# 12V_Buck_Motor.net
KiCad netlist of a schematic drawn in Altium Designer
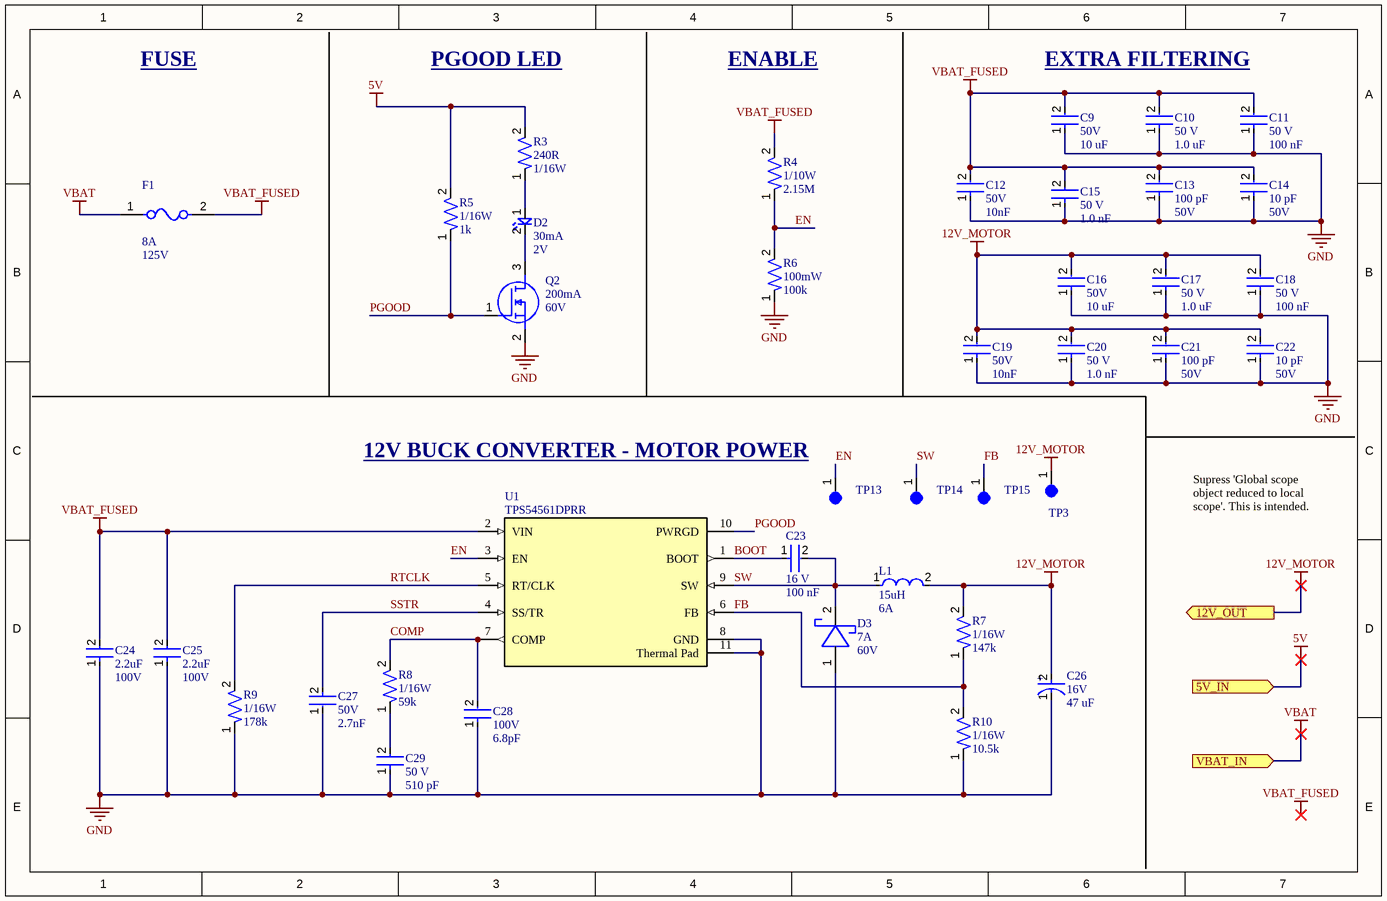
[diagram p0: 12V_Buck_Motor.SchDoc]

(export (version "E")
  (design (tool "Eeschema 10.0.6"))
  (components
    (comp (ref "C9")
      (value "CL32B106KBJNNNE")
      (footprint "CAP-1210")
      (description "CAP CER 10UF 50V X7R 1210")
      (fields (field (name "VOLTAGE") "50V") (field (name "CAPACITANCE") "10 uF"))
      (libsource (lib "JLC_25") (part "CAP-10U-0002"))
    )
    (comp (ref "C10")
      (value "CC0805KKX7R9BB105")
      (footprint "CAP-0805")
      (description "CAP CER 1UF 50V X7R 0805")
      (fields (field (name "VOLTAGE") "50 V") (field (name "CAPACITANCE") "1.0 uF"))
      (libsource (lib "JLC_25") (part "CAP-1U-0001"))
    )
    (comp (ref "C11")
      (value "CC0805KRX7R9BB104")
      (footprint "CAP-0805")
      (description "CAP CER 0.1UF 50V X7R 0805")
      (fields (field (name "VOLTAGE RATING") "50 V") (field (name "CAPACITANCE") "100 nF"))
      (libsource (lib "JLC_25") (part "CAP-0.1U-0002"))
    )
    (comp (ref "C12")
      (value "GRM2195C1H103JA01D")
      (footprint "CAP-0805")
      (description "CAP CER 10000PF 50V C0G/NP0 0805")
      (fields (field (name "VOLTAGE") "50V") (field (name "CAPACITANCE") "10nF"))
      (libsource (lib "JLC_25") (part "CAP-10N-0001"))
    )
    (comp (ref "C13")
      (value "CC0402JRNPO9BN101")
      (footprint "CAP-0402")
      (description "CAP CER 100PF 50V C0G/NPO 0402")
      (fields (field (name "CAPACITANCE") "100 pF") (field (name "VOLTAGE") "50V"))
      (libsource (lib "JLC_25") (part "CAP-100P-0001"))
    )
    (comp (ref "C14")
      (value "CC0402JRNPO9BN100")
      (footprint "CAP-0402")
      (description "CAP CER 10PF 50V C0G/NPO 0402")
      (fields (field (name "CAPACITANCE") "10 pF") (field (name "VOLTAGE") "50V"))
      (libsource (lib "JLC_25") (part "CAP-10P-0001"))
    )
    (comp (ref "C15")
      (value "CC0402KRX7R9BB102")
      (footprint "CAP-0402")
      (description "CAP CER 1000PF 50V X7R 0402")
      (fields (field (name "VOLTAGE") "50 V") (field (name "CAPACITANCE") "1.0 nF"))
      (libsource (lib "JLC_25") (part "CAP-1N-0001"))
    )
    (comp (ref "C16")
      (value "CL32B106KBJNNNE")
      (footprint "CAP-1210")
      (description "CAP CER 10UF 50V X7R 1210")
      (fields (field (name "VOLTAGE") "50V") (field (name "CAPACITANCE") "10 uF"))
      (libsource (lib "JLC_25") (part "CAP-10U-0002"))
    )
    (comp (ref "C17")
      (value "CC0805KKX7R9BB105")
      (footprint "CAP-0805")
      (description "CAP CER 1UF 50V X7R 0805")
      (fields (field (name "VOLTAGE") "50 V") (field (name "CAPACITANCE") "1.0 uF"))
      (libsource (lib "JLC_25") (part "CAP-1U-0001"))
    )
    (comp (ref "C18")
      (value "CC0805KRX7R9BB104")
      (footprint "CAP-0805")
      (description "CAP CER 0.1UF 50V X7R 0805")
      (fields (field (name "VOLTAGE RATING") "50 V") (field (name "CAPACITANCE") "100 nF"))
      (libsource (lib "JLC_25") (part "CAP-0.1U-0002"))
    )
    (comp (ref "C19")
      (value "GRM2195C1H103JA01D")
      (footprint "CAP-0805")
      (description "CAP CER 10000PF 50V C0G/NP0 0805")
      (fields (field (name "VOLTAGE") "50V") (field (name "CAPACITANCE") "10nF"))
      (libsource (lib "JLC_25") (part "CAP-10N-0001"))
    )
    (comp (ref "C20")
      (value "CC0402KRX7R9BB102")
      (footprint "CAP-0402")
      (description "CAP CER 1000PF 50V X7R 0402")
      (fields (field (name "VOLTAGE") "50 V") (field (name "CAPACITANCE") "1.0 nF"))
      (libsource (lib "JLC_25") (part "CAP-1N-0001"))
    )
    (comp (ref "C21")
      (value "CC0402JRNPO9BN101")
      (footprint "CAP-0402")
      (description "CAP CER 100PF 50V C0G/NPO 0402")
      (fields (field (name "CAPACITANCE") "100 pF") (field (name "VOLTAGE") "50V"))
      (libsource (lib "JLC_25") (part "CAP-100P-0001"))
    )
    (comp (ref "C22")
      (value "CC0402JRNPO9BN100")
      (footprint "CAP-0402")
      (description "CAP CER 10PF 50V C0G/NPO 0402")
      (fields (field (name "CAPACITANCE") "10 pF") (field (name "VOLTAGE") "50V"))
      (libsource (lib "JLC_25") (part "CAP-10P-0001"))
    )
    (comp (ref "C23")
      (value "CC0402KRX7R7BB104")
      (footprint "CAP-0402")
      (description "CAP CER 0.1UF 16V X7R 0402")
      (fields (field (name "VOLTAGE RATING") "16 V") (field (name "CAPACITANCE") "100 nF"))
      (libsource (lib "JLC_25") (part "CAP-0.1U-0001"))
    )
    (comp (ref "C24")
      (value "CC1206KKX7R0BB225")
      (footprint "CAP-1206")
      (description "CAP CER 2.2UF 100V X7R 1206")
      (fields (field (name "CAPACITANCE") "2.2uF") (field (name "VOLTAGE") "100V"))
      (libsource (lib "JLC_25") (part "CAP-2.2U-0001"))
    )
    (comp (ref "C25")
      (value "CC1206KKX7R0BB225")
      (footprint "CAP-1206")
      (description "CAP CER 2.2UF 100V X7R 1206")
      (fields (field (name "CAPACITANCE") "2.2uF") (field (name "VOLTAGE") "100V"))
      (libsource (lib "JLC_25") (part "CAP-2.2U-0001"))
    )
    (comp (ref "C26")
      (value "16SVPG47M")
      (footprint "CAP-47U-0001")
      (description "CAP ALUM POLY 47UF 20% 16V SMD")
      (fields (field (name "VOLTAGE") "16V") (field (name "CAPACITANCE") "47 uF"))
      (libsource (lib "JLC_25") (part "CAP-47U-0001"))
    )
    (comp (ref "C27")
      (value "GRM2165C1H272JA01D")
      (footprint "CAP-0805")
      (description "CAP CER 2700PF 50V C0G/NP0 0805")
      (fields (field (name "VOLTAGE") "50V") (field (name "CAPACITANCE") "2.7nF"))
      (libsource (lib "JLC_25") (part "CAP-2.7N-0001"))
    )
    (comp (ref "C28")
      (value "CC0603CRNPO0BN6R8")
      (footprint "CAP-0603")
      (description "CAP CER 6.8PF 100V C0G/NPO 0603")
      (fields (field (name "VOLTAGE") "100V") (field (name "CAPACITANCE") "6.8pF"))
      (libsource (lib "JLC_25") (part "CAP-6.8P-0001"))
    )
    (comp (ref "C29")
      (value "0402N511J500CT")
      (footprint "CAP-0402")
      (description "CAP CER 510PF 50V C0G/NP0 0402")
      (fields (field (name "VOLTAGE") "50 V") (field (name "CAPACITANCE") "510 pF"))
      (libsource (lib "JLC_25") (part "CAP-510P-0001"))
    )
    (comp (ref "D2")
      (value "BL-HKC36G-AV-TRB")
      (footprint "LED-0603")
      (description "LED YELLOW CLEAR 0603 SMD")
      (fields (field (name "FORWARD CURRENT") "30mA") (field (name "FORWARD VOLTAGE") "2V"))
      (libsource (lib "JLC_25") (part "LED-0001"))
    )
    (comp (ref "D3")
      (value "PDS760-13")
      (footprint "DO-POWERDI5")
      (description "DIODE SCHOTTKY 60V 7A POWERDI5")
      (fields (field (name "FORWARD CURRENT") "7A") (field (name "REVERSE VOLTAGE (DC)") "60V"))
      (libsource (lib "JLC_25") (part "DIO-SCHOTTKY-0001"))
    )
    (comp (ref "F1")
      (value "01550900M")
      (footprint "FUSE-0001")
      (description "FUSE BLOK CARTRIDGE 125V 10A SMD")
      (fields (field (name "FUSE CURRENT") "8A") (field (name "VOLTAGE RATING") "125V"))
      (libsource (lib "JLC_25") (part "FUSE-0001"))
    )
    (comp (ref "L1")
      (value "CSAD1010-150M")
      (footprint "IND-15U-0002")
      (description "SMD MOLDING POWER CHOKE")
      (fields (field (name "INDUCTANCE") "15uH") (field (name "CURRENT RATING") "6A"))
      (libsource (lib "JLC_25") (part "IND-15U-0002-NoJLC"))
    )
    (comp (ref "Q2")
      (value "T2N7002AK,LM")
      (footprint "IC-SOT23-3")
      (description "MOSFET N-CH 60V 200MA SOT23")
      (fields (field (name "CONTINUOUS CURRENT") "200mA") (field (name "VOLTAGE") "60V"))
      (libsource (lib "JLC_25") (part "NMOS-200MA-0001"))
    )
    (comp (ref "R3")
      (value "RC0402FR-07240RL")
      (footprint "RES-0402")
      (description "240R 0.063W 1% 0402 (1005 Metric)  SMD")
      (fields
        (field (name "TOLERANCE") "1%")
        (field (name "RESISTANCE") "240R")
        (field (name "POWER") "1/16W")
      )
      (libsource (lib "JLC_25") (part "RES-240-0001"))
    )
    (comp (ref "R4")
      (value "RC0603FR-072M15L")
      (footprint "RES-0603")
      (description "RES SMD 2.15M OHM 1% 1/10W 0603")
      (fields
        (field (name "TOLERANCE") "1%")
        (field (name "POWER") "1/10W")
        (field (name "RESISTANCE") "2.15M")
      )
      (libsource (lib "JLC_25") (part "RES-2.15M-0001"))
    )
    (comp (ref "R5")
      (value "RC0402FR-071KL")
      (footprint "RES-0402")
      (description "RES 1K OHM 1% 1/16W 0402")
      (fields (field (name "TOLERANCE") "1%") (field (name "POWER") "1/16W") (field (name "RESISTANCE") "1k"))
      (libsource (lib "JLC_25") (part "RES-1k-0001"))
    )
    (comp (ref "R6")
      (value "RC0603FR-07100KL")
      (footprint "RES-0603")
      (description "RES SMD 100K OHM 1% 1/10W 0603")
      (fields
        (field (name "TOLERANCE") "1%")
        (field (name "POWER") "100mW")
        (field (name "RESISTANCE") "100k")
      )
      (libsource (lib "JLC_25") (part "RES-100k-0001"))
    )
    (comp (ref "R7")
      (value "RC0402FR-07147KL")
      (footprint "RES-0402")
      (description "RES 147K OHM 1% 1/16W 0402")
      (fields
        (field (name "TOLERANCE") "1%")
        (field (name "POWER") "1/16W")
        (field (name "RESISTANCE") "147k")
      )
      (libsource (lib "JLC_25") (part "RES-147k-0001"))
    )
    (comp (ref "R8")
      (value "RC0402FR-0759KL")
      (footprint "RES-0402")
      (description "RES 59K OHM 1% 1/16W 0402")
      (fields
        (field (name "TOLERANCE") "1%")
        (field (name "POWER") "1/16W")
        (field (name "RESISTANCE") "59k")
      )
      (libsource (lib "JLC_25") (part "RES-59k-0001"))
    )
    (comp (ref "R9")
      (value "RTT021783FTH")
      (footprint "RES-0402")
      (description "62.5mW Thick Film Resistors 50V ±100ppm/℃ ±1% 178kΩ 0402 Chip Resistor - Surface Mount ROHS")
      (fields
        (field (name "TOLERANCE") "1%")
        (field (name "POWER") "1/16W")
        (field (name "RESISTANCE") "178k")
      )
      (libsource (lib "JLC_25") (part "RES-178k-0001"))
    )
    (comp (ref "R10")
      (value "RC0402FR-0710K5L")
      (footprint "RES-0402")
      (description "RES 10.5K OHM 1% 1/16W 0402")
      (fields
        (field (name "TOLERANCE") "1%")
        (field (name "POWER") "1/16W")
        (field (name "RESISTANCE") "10.5k")
      )
      (libsource (lib "JLC_25") (part "RES-10.5k-0001"))
    )
    (comp (ref "TP3")
      (value "5003")
      (footprint "TEST-POINT-0001")
      (description "Oranange PC Test Point, Miniature Phoisphor Bronze Silver Plating Through Hole Mounting Type")
      (libsource (lib "*") (part "TEST-POINT-0001"))
    )
    (comp (ref "TP13")
      (value "5003")
      (footprint "TEST-POINT-0001")
      (description "Oranange PC Test Point, Miniature Phoisphor Bronze Silver Plating Through Hole Mounting Type")
      (libsource (lib "*") (part "TEST-POINT-0001"))
    )
    (comp (ref "TP14")
      (value "5003")
      (footprint "TEST-POINT-0001")
      (description "Oranange PC Test Point, Miniature Phoisphor Bronze Silver Plating Through Hole Mounting Type")
      (libsource (lib "*") (part "TEST-POINT-0001"))
    )
    (comp (ref "TP15")
      (value "5003")
      (footprint "TEST-POINT-0001")
      (description "Oranange PC Test Point, Miniature Phoisphor Bronze Silver Plating Through Hole Mounting Type")
      (libsource (lib "*") (part "TEST-POINT-0001"))
    )
    (comp (ref "U1")
      (value "TPS54561DPRR")
      (footprint "IC-10WSON")
      (description "IC REG BUCK ADJ 5A 10WSON")
      (libsource (lib "JLC_25") (part "IC-BUCK-0001"))
    )
  )
  (nets
    (net (code "1") (name "/BOOT") (class "Default")
      (node (ref "C23") (pin "1") (pinfunction "1_1") (pintype "passive"))
      (node (ref "U1") (pin "1") (pinfunction "BOOT_1") (pintype "output"))
    )
    (net (code "2") (name "/COMP") (class "Default")
      (node (ref "C28") (pin "2") (pinfunction "2_2") (pintype "passive"))
      (node (ref "R8") (pin "2") (pinfunction "2_2") (pintype "passive"))
      (node (ref "U1") (pin "7") (pinfunction "COMP_7") (pintype "output"))
    )
    (net (code "3") (name "/EN") (class "Default")
      (node (ref "R4") (pin "1") (pinfunction "1_1") (pintype "passive"))
      (node (ref "R6") (pin "2") (pinfunction "2_2") (pintype "passive"))
      (node (ref "TP13") (pin "1") (pinfunction "0_1") (pintype "passive"))
      (node (ref "U1") (pin "3") (pinfunction "EN_3") (pintype "input"))
    )
    (net (code "4") (name "/FB") (class "Default")
      (node (ref "R10") (pin "2") (pinfunction "2_2") (pintype "passive"))
      (node (ref "R7") (pin "1") (pinfunction "1_1") (pintype "passive"))
      (node (ref "TP15") (pin "1") (pinfunction "0_1") (pintype "passive"))
      (node (ref "U1") (pin "6") (pinfunction "FB_6") (pintype "input"))
    )
    (net (code "5") (name "/PGOOD") (class "Default")
      (node (ref "Q2") (pin "1") (pinfunction "G_1") (pintype "passive"))
      (node (ref "R5") (pin "1") (pinfunction "1_1") (pintype "passive"))
      (node (ref "U1") (pin "10") (pinfunction "PWRGD_10") (pintype "open_collector"))
    )
    (net (code "6") (name "/RTCLK") (class "Default")
      (node (ref "R9") (pin "2") (pinfunction "2_2") (pintype "passive"))
      (node (ref "U1") (pin "5") (pinfunction "RT/CLK_5") (pintype "input"))
    )
    (net (code "7") (name "/SSTR") (class "Default")
      (node (ref "C27") (pin "2") (pinfunction "2_2") (pintype "passive"))
      (node (ref "U1") (pin "4") (pinfunction "SS/TR_4") (pintype "input"))
    )
    (net (code "8") (name "/SW") (class "Default")
      (node (ref "C23") (pin "2") (pinfunction "2_2") (pintype "passive"))
      (node (ref "D3") (pin "2") (pinfunction "ANODE_2") (pintype "passive"))
      (node (ref "L1") (pin "1") (pinfunction "1_1") (pintype "passive"))
      (node (ref "TP14") (pin "1") (pinfunction "0_1") (pintype "passive"))
      (node (ref "U1") (pin "9") (pinfunction "SW_9") (pintype "input"))
    )
    (net (code "9") (name "5V") (class "Default")
      (node (ref "R3") (pin "2") (pinfunction "2_2") (pintype "passive"))
      (node (ref "R5") (pin "2") (pinfunction "2_2") (pintype "passive"))
    )
    (net (code "10") (name "12V_MOTOR") (class "Default")
      (node (ref "C16") (pin "2") (pinfunction "2_2") (pintype "passive"))
      (node (ref "C17") (pin "2") (pinfunction "2_2") (pintype "passive"))
      (node (ref "C18") (pin "2") (pinfunction "2_2") (pintype "passive"))
      (node (ref "C19") (pin "2") (pinfunction "2_2") (pintype "passive"))
      (node (ref "C20") (pin "2") (pinfunction "2_2") (pintype "passive"))
      (node (ref "C21") (pin "2") (pinfunction "2_2") (pintype "passive"))
      (node (ref "C22") (pin "2") (pinfunction "2_2") (pintype "passive"))
      (node (ref "C26") (pin "2") (pinfunction "A_2") (pintype "passive"))
      (node (ref "L1") (pin "2") (pinfunction "2_2") (pintype "passive"))
      (node (ref "R7") (pin "2") (pinfunction "2_2") (pintype "passive"))
      (node (ref "TP3") (pin "1") (pinfunction "0_1") (pintype "passive"))
    )
    (net (code "11") (name "GND") (class "Default")
      (node (ref "C10") (pin "1") (pinfunction "1_1") (pintype "passive"))
      (node (ref "C11") (pin "1") (pinfunction "1_1") (pintype "passive"))
      (node (ref "C12") (pin "1") (pinfunction "1_1") (pintype "passive"))
      (node (ref "C13") (pin "1") (pinfunction "1_1") (pintype "passive"))
      (node (ref "C14") (pin "1") (pinfunction "1_1") (pintype "passive"))
      (node (ref "C15") (pin "1") (pinfunction "1_1") (pintype "passive"))
      (node (ref "C16") (pin "1") (pinfunction "1_1") (pintype "passive"))
      (node (ref "C17") (pin "1") (pinfunction "1_1") (pintype "passive"))
      (node (ref "C18") (pin "1") (pinfunction "1_1") (pintype "passive"))
      (node (ref "C19") (pin "1") (pinfunction "1_1") (pintype "passive"))
      (node (ref "C20") (pin "1") (pinfunction "1_1") (pintype "passive"))
      (node (ref "C21") (pin "1") (pinfunction "1_1") (pintype "passive"))
      (node (ref "C22") (pin "1") (pinfunction "1_1") (pintype "passive"))
      (node (ref "C24") (pin "1") (pinfunction "1_1") (pintype "passive"))
      (node (ref "C25") (pin "1") (pinfunction "1_1") (pintype "passive"))
      (node (ref "C26") (pin "1") (pinfunction "C_1") (pintype "passive"))
      (node (ref "C27") (pin "1") (pinfunction "1_1") (pintype "passive"))
      (node (ref "C28") (pin "1") (pinfunction "1_1") (pintype "passive"))
      (node (ref "C29") (pin "1") (pinfunction "1_1") (pintype "passive"))
      (node (ref "C9") (pin "1") (pinfunction "1_1") (pintype "passive"))
      (node (ref "D3") (pin "1") (pinfunction "CATHODE_1") (pintype "passive"))
      (node (ref "Q2") (pin "2") (pinfunction "S_2") (pintype "passive"))
      (node (ref "R10") (pin "1") (pinfunction "1_1") (pintype "passive"))
      (node (ref "R6") (pin "1") (pinfunction "1_1") (pintype "passive"))
      (node (ref "R9") (pin "1") (pinfunction "1_1") (pintype "passive"))
      (node (ref "U1") (pin "11") (pinfunction "Thermal_Pad_11") (pintype "power_in"))
      (node (ref "U1") (pin "8") (pinfunction "GND_8") (pintype "power_in"))
    )
    (net (code "12") (name "Net-(C29-Pad2)") (class "Default")
      (node (ref "C29") (pin "2") (pinfunction "2_2") (pintype "passive"))
      (node (ref "R8") (pin "1") (pinfunction "1_1") (pintype "passive"))
    )
    (net (code "13") (name "Net-(D2-Pad1)") (class "Default")
      (node (ref "D2") (pin "1") (pinfunction "1_1") (pintype "passive"))
      (node (ref "R3") (pin "1") (pinfunction "1_1") (pintype "passive"))
    )
    (net (code "14") (name "Net-(Q2-D)") (class "Default")
      (node (ref "D2") (pin "2") (pinfunction "2_2") (pintype "passive"))
      (node (ref "Q2") (pin "3") (pinfunction "D_3") (pintype "passive"))
    )
    (net (code "15") (name "VBAT") (class "Default")
      (node (ref "F1") (pin "1") (pinfunction "1_1") (pintype "passive"))
    )
    (net (code "16") (name "VBAT_FUSED") (class "Default")
      (node (ref "C10") (pin "2") (pinfunction "2_2") (pintype "passive"))
      (node (ref "C11") (pin "2") (pinfunction "2_2") (pintype "passive"))
      (node (ref "C12") (pin "2") (pinfunction "2_2") (pintype "passive"))
      (node (ref "C13") (pin "2") (pinfunction "2_2") (pintype "passive"))
      (node (ref "C14") (pin "2") (pinfunction "2_2") (pintype "passive"))
      (node (ref "C15") (pin "2") (pinfunction "2_2") (pintype "passive"))
      (node (ref "C24") (pin "2") (pinfunction "2_2") (pintype "passive"))
      (node (ref "C25") (pin "2") (pinfunction "2_2") (pintype "passive"))
      (node (ref "C9") (pin "2") (pinfunction "2_2") (pintype "passive"))
      (node (ref "F1") (pin "2") (pinfunction "2_2") (pintype "passive"))
      (node (ref "R4") (pin "2") (pinfunction "2_2") (pintype "passive"))
      (node (ref "U1") (pin "2") (pinfunction "VIN_2") (pintype "input"))
    )
  )
)
